# ampInputBreakOutV1.net
KiCad netlist of a schematic drawn in Altium Designer
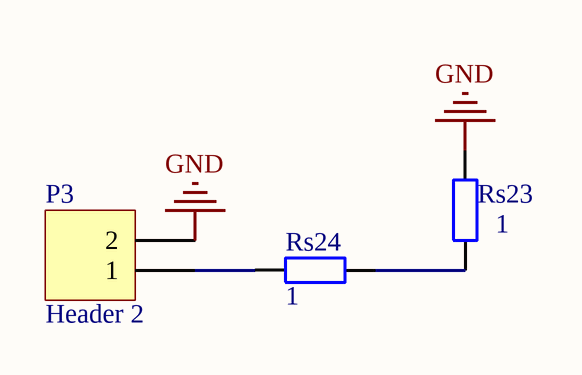
[diagram p0: ampInputBreakOutV1.SchDoc]

(export (version "E")
  (design (tool "Eeschema 10.0.6"))
  (components
    (comp (ref "P3")
      (value "Header 2")
      (footprint "HDR1X2")
      (description "Header, 2-Pin")
      (fields (field (name "PUBLISHER") "Altium Limited"))
      (libsource (lib "Miscellaneous Connectors") (part "Header 2"))
    )
    (comp (ref "Rs23")
      (value "1")
      (footprint "AXIAL-0.4 PCBK")
      (description "Resistor")
      (fields (field (name "PUBLISHER") "Altium Limited"))
      (libsource (lib "") (part "Res PCBK_1"))
    )
    (comp (ref "Rs24")
      (value "1")
      (footprint "AXIAL-0.4 PCBK")
      (description "Resistor")
      (fields (field (name "PUBLISHER") "Altium Limited"))
      (libsource (lib "pcb_kursus_lib2020") (part "Res PCBK"))
    )
  )
  (nets
    (net (code "1") (name "GND") (class "Default")
      (node (ref "P3") (pin "2") (pinfunction "2_2") (pintype "passive"))
      (node (ref "Rs23") (pin "2") (pinfunction "2_2") (pintype "passive"))
    )
    (net (code "2") (name "Net-(P3-Pad1)") (class "Default")
      (node (ref "P3") (pin "1") (pinfunction "1_1") (pintype "passive"))
      (node (ref "Rs24") (pin "1") (pinfunction "1_1") (pintype "passive"))
    )
    (net (code "3") (name "Net-(Rs23-Pad1)") (class "Default")
      (node (ref "Rs23") (pin "1") (pinfunction "1_1") (pintype "passive"))
      (node (ref "Rs24") (pin "2") (pinfunction "2_2") (pintype "passive"))
    )
  )
)
